# SchematicV2.net
KiCad netlist of a schematic drawn in EAGLE
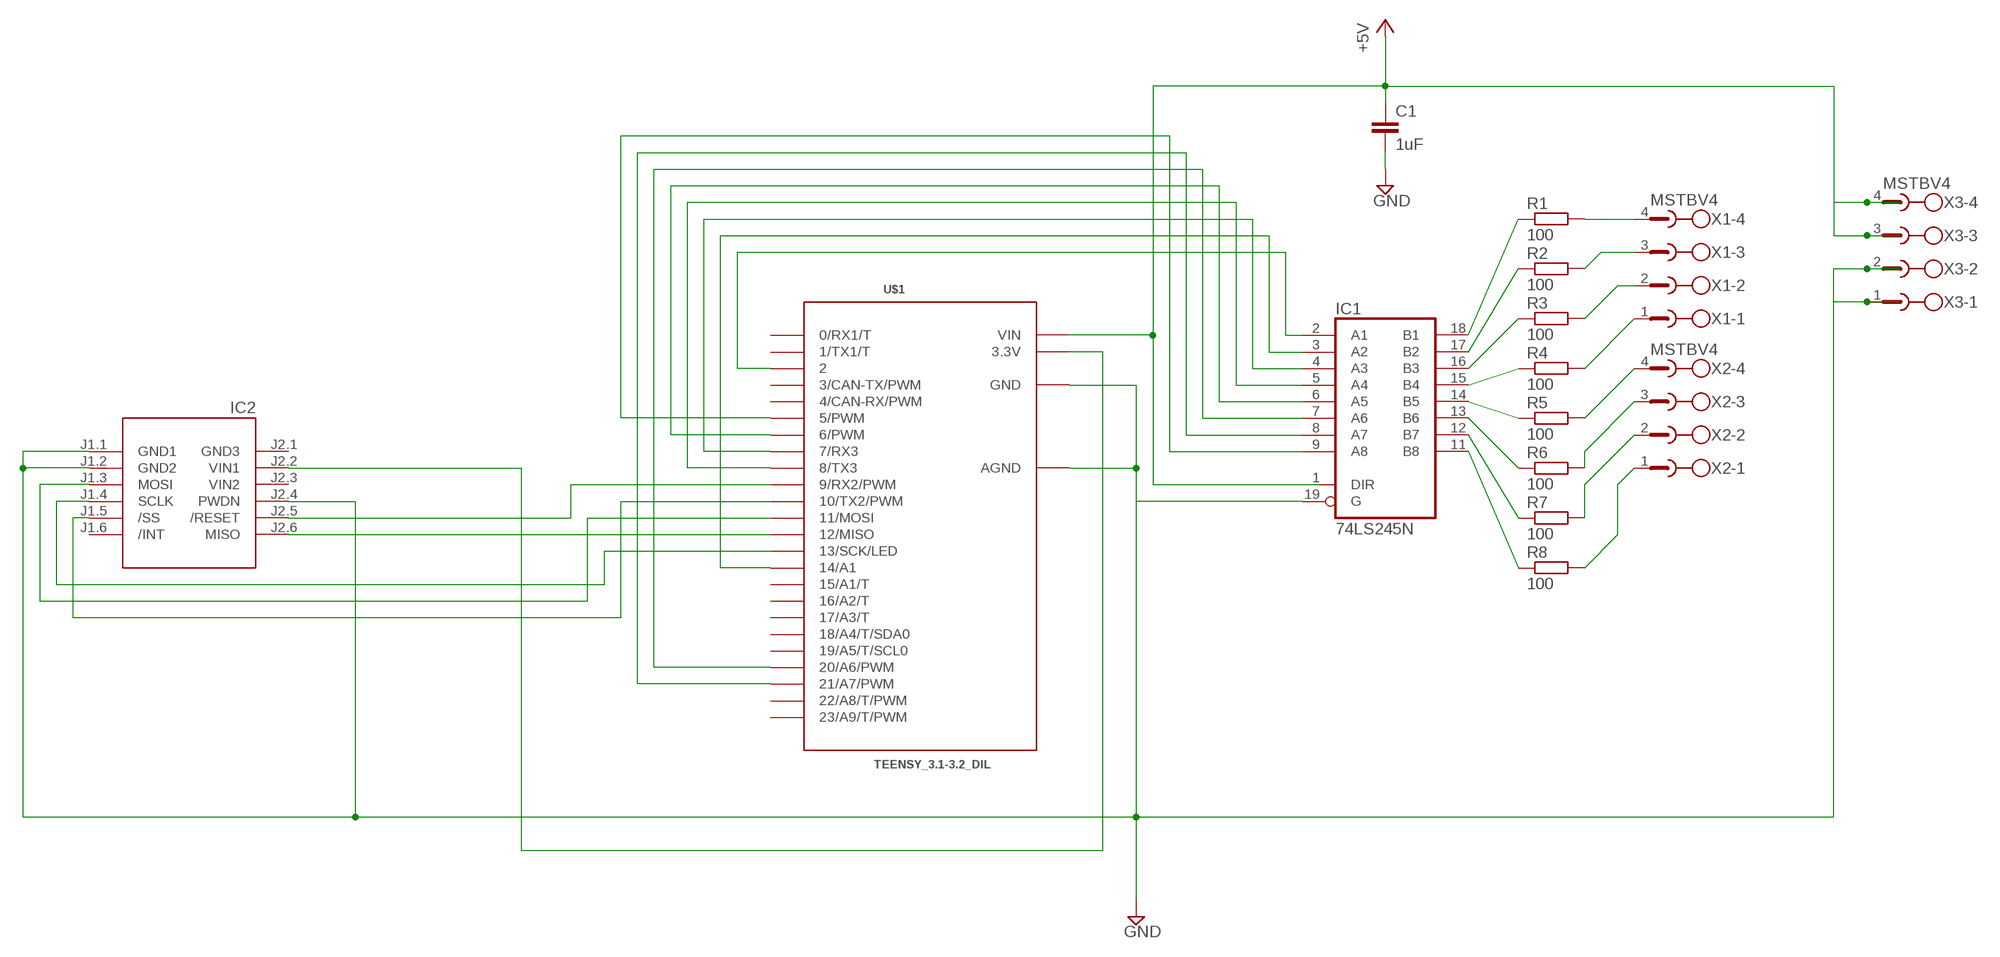
[diagram p0: schematic, sheet 1]

(export (version "E")
  (design (tool "Eeschema 10.0.6"))
  (components
    (comp (ref "C1")
      (value "1uF")
      (footprint "eagle-import:C050-035X075")
      (libsource (lib "eagle-import") (part "C-EU050-035X075"))
    )
    (comp (ref "IC1")
      (value "74LS245N")
      (footprint "eagle-import:DIL20")
      (libsource (lib "eagle-import") (part "74245NLS"))
    )
    (comp (ref "IC2")
      (value "WIZ820IO_DEVICE'DUAL-IN-LINE'")
      (footprint "eagle-import:WIZ820IO")
      (libsource (lib "eagle-import") (part "WIZ820IO_DEVICE'DUAL-IN-LINE'"))
    )
    (comp (ref "R1")
      (value "100")
      (footprint "eagle-import:0207_7")
      (libsource (lib "eagle-import") (part "R-EU_0207/7"))
    )
    (comp (ref "R2")
      (value "100")
      (footprint "eagle-import:0207_7")
      (libsource (lib "eagle-import") (part "R-EU_0207/7"))
    )
    (comp (ref "R3")
      (value "100")
      (footprint "eagle-import:0207_7")
      (libsource (lib "eagle-import") (part "R-EU_0207/7"))
    )
    (comp (ref "R4")
      (value "100")
      (footprint "eagle-import:0207_7")
      (libsource (lib "eagle-import") (part "R-EU_0207/7"))
    )
    (comp (ref "R5")
      (value "100")
      (footprint "eagle-import:0207_7")
      (libsource (lib "eagle-import") (part "R-EU_0207/7"))
    )
    (comp (ref "R6")
      (value "100")
      (footprint "eagle-import:0207_7")
      (libsource (lib "eagle-import") (part "R-EU_0207/7"))
    )
    (comp (ref "R7")
      (value "100")
      (footprint "eagle-import:0207_7")
      (libsource (lib "eagle-import") (part "R-EU_0207/7"))
    )
    (comp (ref "R8")
      (value "100")
      (footprint "eagle-import:0207_7")
      (libsource (lib "eagle-import") (part "R-EU_0207/7"))
    )
    (comp (ref "U$1")
      (value "TEENSY_3.1-3.2_DIL")
      (footprint "eagle-import:TEENSY_3.0-3.2&LC_DIL")
      (libsource (lib "eagle-import") (part "TEENSY_3.1-3.2_DIL"))
    )
    (comp (ref "X1")
      (value "MSTBV4")
      (footprint "eagle-import:MSTBV4")
      (fields (field (name "MPN") "MSTBV 2,5/4-GF-5.08"))
      (libsource (lib "eagle-import") (part "MSTBV4"))
    )
    (comp (ref "X2")
      (value "MSTBV4")
      (footprint "eagle-import:MSTBV4")
      (fields (field (name "MPN") "MSTBV 2,5/4-GF-5.08"))
      (libsource (lib "eagle-import") (part "MSTBV4"))
    )
    (comp (ref "X3")
      (value "MSTBV4")
      (footprint "eagle-import:MSTBV4")
      (fields (field (name "MPN") "MSTBV 2,5/4-GF-5.08"))
      (libsource (lib "eagle-import") (part "MSTBV4"))
    )
  )
  (nets
    (net (code "1") (name "+5V") (class "Default")
      (node (ref "C1") (pin "1") (pinfunction "1_1") (pintype "passive"))
      (node (ref "U$1") (pin "VIN") (pinfunction "VIN_VIN") (pintype "power_in"))
      (node (ref "X3") (pin "3") (pinfunction "1_3") (pintype "passive"))
      (node (ref "X3") (pin "4") (pinfunction "1_4") (pintype "passive"))
    )
    (net (code "2") (name "/GND3") (class "Default")
      (node (ref "IC2") (pin "J2.1") (pinfunction "GND3_J2.1") (pintype "power_in"))
    )
    (net (code "3") (name "/VIN2") (class "Default")
      (node (ref "IC2") (pin "J2.3") (pinfunction "VIN2_J2.3") (pintype "power_in"))
    )
    (net (code "4") (name "GND") (class "Default")
      (node (ref "C1") (pin "2") (pinfunction "2_2") (pintype "passive"))
      (node (ref "IC1") (pin "19") (pinfunction "G_19") (pintype "input"))
      (node (ref "IC2") (pin "J1.1") (pinfunction "GND1_J1.1") (pintype "power_in"))
      (node (ref "IC2") (pin "J1.2") (pinfunction "GND2_J1.2") (pintype "power_in"))
      (node (ref "IC2") (pin "J2.4") (pinfunction "PWDN_J2.4") (pintype "input"))
      (node (ref "U$1") (pin "AGND") (pinfunction "AGND_AGND") (pintype "power_in"))
      (node (ref "U$1") (pin "GND") (pinfunction "GND_GND") (pintype "power_in"))
      (node (ref "X3") (pin "1") (pinfunction "1_1") (pintype "passive"))
      (node (ref "X3") (pin "2") (pinfunction "1_2") (pintype "passive"))
    )
    (net (code "5") (name "Net-(IC1A-A1)") (class "Default")
      (node (ref "IC1") (pin "2") (pinfunction "A1_2") (pintype "bidirectional"))
      (node (ref "U$1") (pin "2") (pinfunction "2_2") (pintype "bidirectional"))
    )
    (net (code "6") (name "Net-(IC1A-A2)") (class "Default")
      (node (ref "IC1") (pin "3") (pinfunction "A2_3") (pintype "bidirectional"))
      (node (ref "U$1") (pin "14/A0") (pinfunction "14/A1_14/A0") (pintype "bidirectional"))
    )
    (net (code "7") (name "Net-(IC1A-A3)") (class "Default")
      (node (ref "IC1") (pin "4") (pinfunction "A3_4") (pintype "bidirectional"))
      (node (ref "U$1") (pin "7") (pinfunction "7/RX3_7") (pintype "bidirectional"))
    )
    (net (code "8") (name "Net-(IC1A-A4)") (class "Default")
      (node (ref "IC1") (pin "5") (pinfunction "A4_5") (pintype "bidirectional"))
      (node (ref "U$1") (pin "8") (pinfunction "8/TX3_8") (pintype "bidirectional"))
    )
    (net (code "9") (name "Net-(IC1A-A5)") (class "Default")
      (node (ref "IC1") (pin "6") (pinfunction "A5_6") (pintype "bidirectional"))
      (node (ref "U$1") (pin "6") (pinfunction "6/PWM_6") (pintype "bidirectional"))
    )
    (net (code "10") (name "Net-(IC1A-A6)") (class "Default")
      (node (ref "IC1") (pin "7") (pinfunction "A6_7") (pintype "bidirectional"))
      (node (ref "U$1") (pin "20/A6") (pinfunction "20/A6/PWM_20/A6") (pintype "bidirectional"))
    )
    (net (code "11") (name "Net-(IC1A-A7)") (class "Default")
      (node (ref "IC1") (pin "8") (pinfunction "A7_8") (pintype "bidirectional"))
      (node (ref "U$1") (pin "21/A7") (pinfunction "21/A7/PWM_21/A7") (pintype "bidirectional"))
    )
    (net (code "12") (name "Net-(IC1A-A8)") (class "Default")
      (node (ref "IC1") (pin "9") (pinfunction "A8_9") (pintype "bidirectional"))
      (node (ref "U$1") (pin "5") (pinfunction "5/PWM_5") (pintype "bidirectional"))
    )
    (net (code "13") (name "Net-(IC1A-B1)") (class "Default")
      (node (ref "IC1") (pin "18") (pinfunction "B1_18") (pintype "bidirectional"))
      (node (ref "R1") (pin "1") (pinfunction "1_1") (pintype "passive"))
    )
    (net (code "14") (name "Net-(IC1A-B2)") (class "Default")
      (node (ref "IC1") (pin "17") (pinfunction "B2_17") (pintype "bidirectional"))
      (node (ref "R2") (pin "1") (pinfunction "1_1") (pintype "passive"))
    )
    (net (code "15") (name "Net-(IC1A-B3)") (class "Default")
      (node (ref "IC1") (pin "16") (pinfunction "B3_16") (pintype "bidirectional"))
      (node (ref "R3") (pin "1") (pinfunction "1_1") (pintype "passive"))
    )
    (net (code "16") (name "Net-(IC1A-B4)") (class "Default")
      (node (ref "IC1") (pin "15") (pinfunction "B4_15") (pintype "bidirectional"))
      (node (ref "R4") (pin "1") (pinfunction "1_1") (pintype "passive"))
    )
    (net (code "17") (name "Net-(IC1A-B5)") (class "Default")
      (node (ref "IC1") (pin "14") (pinfunction "B5_14") (pintype "bidirectional"))
      (node (ref "R5") (pin "1") (pinfunction "1_1") (pintype "passive"))
    )
    (net (code "18") (name "Net-(IC1A-B6)") (class "Default")
      (node (ref "IC1") (pin "13") (pinfunction "B6_13") (pintype "bidirectional"))
      (node (ref "R6") (pin "1") (pinfunction "1_1") (pintype "passive"))
    )
    (net (code "19") (name "Net-(IC1A-B7)") (class "Default")
      (node (ref "IC1") (pin "12") (pinfunction "B7_12") (pintype "bidirectional"))
      (node (ref "R7") (pin "1") (pinfunction "1_1") (pintype "passive"))
    )
    (net (code "20") (name "Net-(IC1A-B8)") (class "Default")
      (node (ref "IC1") (pin "11") (pinfunction "B8_11") (pintype "bidirectional"))
      (node (ref "R8") (pin "1") (pinfunction "1_1") (pintype "passive"))
    )
    (net (code "21") (name "Net-(IC2-MISO)") (class "Default")
      (node (ref "IC2") (pin "J2.6") (pinfunction "MISO_J2.6") (pintype "output"))
      (node (ref "U$1") (pin "12") (pinfunction "12/MISO_12") (pintype "bidirectional"))
    )
    (net (code "22") (name "Net-(IC2-MOSI)") (class "Default")
      (node (ref "IC2") (pin "J1.3") (pinfunction "MOSI_J1.3") (pintype "input"))
      (node (ref "U$1") (pin "11") (pinfunction "11/MOSI_11") (pintype "bidirectional"))
    )
    (net (code "23") (name "Net-(IC2-SCLK)") (class "Default")
      (node (ref "IC2") (pin "J1.4") (pinfunction "SCLK_J1.4") (pintype "input"))
      (node (ref "U$1") (pin "13") (pinfunction "13/SCK/LED_13") (pintype "bidirectional"))
    )
    (net (code "24") (name "Net-(IC2-VIN1)") (class "Default")
      (node (ref "IC2") (pin "J2.2") (pinfunction "VIN1_J2.2") (pintype "power_in"))
      (node (ref "U$1") (pin "3.3V") (pinfunction "3.3V_3.3V") (pintype "power_in"))
    )
    (net (code "25") (name "Net-(IC2-{slash}RESET)") (class "Default")
      (node (ref "IC2") (pin "J2.5") (pinfunction "/RESET_J2.5") (pintype "input"))
      (node (ref "U$1") (pin "9") (pinfunction "9/RX2/PWM_9") (pintype "bidirectional"))
    )
    (net (code "26") (name "Net-(IC2-{slash}SS)") (class "Default")
      (node (ref "IC2") (pin "J1.5") (pinfunction "/SS_J1.5") (pintype "input"))
      (node (ref "U$1") (pin "10") (pinfunction "10/TX2/PWM_10") (pintype "bidirectional"))
    )
    (net (code "27") (name "Net-(R4-Pad2)") (class "Default")
      (node (ref "R4") (pin "2") (pinfunction "2_2") (pintype "passive"))
      (node (ref "X1") (pin "1") (pinfunction "1_1") (pintype "passive"))
    )
    (net (code "28") (name "Net-(R8-Pad2)") (class "Default")
      (node (ref "R8") (pin "2") (pinfunction "2_2") (pintype "passive"))
      (node (ref "X2") (pin "1") (pinfunction "1_1") (pintype "passive"))
    )
    (net (code "29") (name "Net-(X1B-1)") (class "Default")
      (node (ref "R3") (pin "2") (pinfunction "2_2") (pintype "passive"))
      (node (ref "X1") (pin "2") (pinfunction "1_2") (pintype "passive"))
    )
    (net (code "30") (name "Net-(X1C-1)") (class "Default")
      (node (ref "R2") (pin "2") (pinfunction "2_2") (pintype "passive"))
      (node (ref "X1") (pin "3") (pinfunction "1_3") (pintype "passive"))
    )
    (net (code "31") (name "Net-(X1D-1)") (class "Default")
      (node (ref "R1") (pin "2") (pinfunction "2_2") (pintype "passive"))
      (node (ref "X1") (pin "4") (pinfunction "1_4") (pintype "passive"))
    )
    (net (code "32") (name "Net-(X2B-1)") (class "Default")
      (node (ref "R7") (pin "2") (pinfunction "2_2") (pintype "passive"))
      (node (ref "X2") (pin "2") (pinfunction "1_2") (pintype "passive"))
    )
    (net (code "33") (name "Net-(X2C-1)") (class "Default")
      (node (ref "R6") (pin "2") (pinfunction "2_2") (pintype "passive"))
      (node (ref "X2") (pin "3") (pinfunction "1_3") (pintype "passive"))
    )
    (net (code "34") (name "Net-(X2D-1)") (class "Default")
      (node (ref "R5") (pin "2") (pinfunction "2_2") (pintype "passive"))
      (node (ref "X2") (pin "4") (pinfunction "1_4") (pintype "passive"))
    )
    (net (code "35") (name "unconnected-(IC1A-DIR-Pad1)") (class "Default")
      (node (ref "IC1") (pin "1") (pinfunction "DIR_1") (pintype "input"))
    )
    (net (code "36") (name "unconnected-(IC2-{slash}INT-PadJ1.6)") (class "Default")
      (node (ref "IC2") (pin "J1.6") (pinfunction "/INT_J1.6") (pintype "output"))
    )
    (net (code "37") (name "unconnected-(U$1-0{slash}RX1{slash}T-Pad0)") (class "Default")
      (node (ref "U$1") (pin "0") (pinfunction "0/RX1/T_0") (pintype "bidirectional"))
    )
    (net (code "38") (name "unconnected-(U$1-1{slash}TX1{slash}T-Pad1)") (class "Default")
      (node (ref "U$1") (pin "1") (pinfunction "1/TX1/T_1") (pintype "bidirectional"))
    )
    (net (code "39") (name "unconnected-(U$1-3{slash}CAN-TX{slash}PWM-Pad3)") (class "Default")
      (node (ref "U$1") (pin "3") (pinfunction "3/CAN-TX/PWM_3") (pintype "bidirectional"))
    )
    (net (code "40") (name "unconnected-(U$1-4{slash}CAN-RX{slash}PWM-Pad4)") (class "Default")
      (node (ref "U$1") (pin "4") (pinfunction "4/CAN-RX/PWM_4") (pintype "bidirectional"))
    )
    (net (code "41") (name "unconnected-(U$1-15{slash}A1{slash}T-Pad15{slash}A1)") (class "Default")
      (node (ref "U$1") (pin "15/A1") (pinfunction "15/A1/T_15/A1") (pintype "bidirectional"))
    )
    (net (code "42") (name "unconnected-(U$1-16{slash}A2{slash}T-Pad16{slash}A2)") (class "Default")
      (node (ref "U$1") (pin "16/A2") (pinfunction "16/A2/T_16/A2") (pintype "bidirectional"))
    )
    (net (code "43") (name "unconnected-(U$1-17{slash}A3{slash}T-Pad17{slash}A3)") (class "Default")
      (node (ref "U$1") (pin "17/A3") (pinfunction "17/A3/T_17/A3") (pintype "bidirectional"))
    )
    (net (code "44") (name "unconnected-(U$1-18{slash}A4{slash}T{slash}SDA0-Pad18{slash}A4)") (class "Default")
      (node (ref "U$1") (pin "18/A4") (pinfunction "18/A4/T/SDA0_18/A4") (pintype "bidirectional"))
    )
    (net (code "45") (name "unconnected-(U$1-19{slash}A5{slash}T{slash}SCL0-Pad19{slash}A5)") (class "Default")
      (node (ref "U$1") (pin "19/A5") (pinfunction "19/A5/T/SCL0_19/A5") (pintype "bidirectional"))
    )
    (net (code "46") (name "unconnected-(U$1-22{slash}A8{slash}T{slash}PWM-Pad22{slash}A8)") (class "Default")
      (node (ref "U$1") (pin "22/A8") (pinfunction "22/A8/T/PWM_22/A8") (pintype "bidirectional"))
    )
    (net (code "47") (name "unconnected-(U$1-23{slash}A9{slash}T{slash}PWM-Pad23{slash}A9)") (class "Default")
      (node (ref "U$1") (pin "23/A9") (pinfunction "23/A9/T/PWM_23/A9") (pintype "bidirectional"))
    )
  )
)
